# MCU.net
KiCad netlist of a schematic drawn in Altium Designer
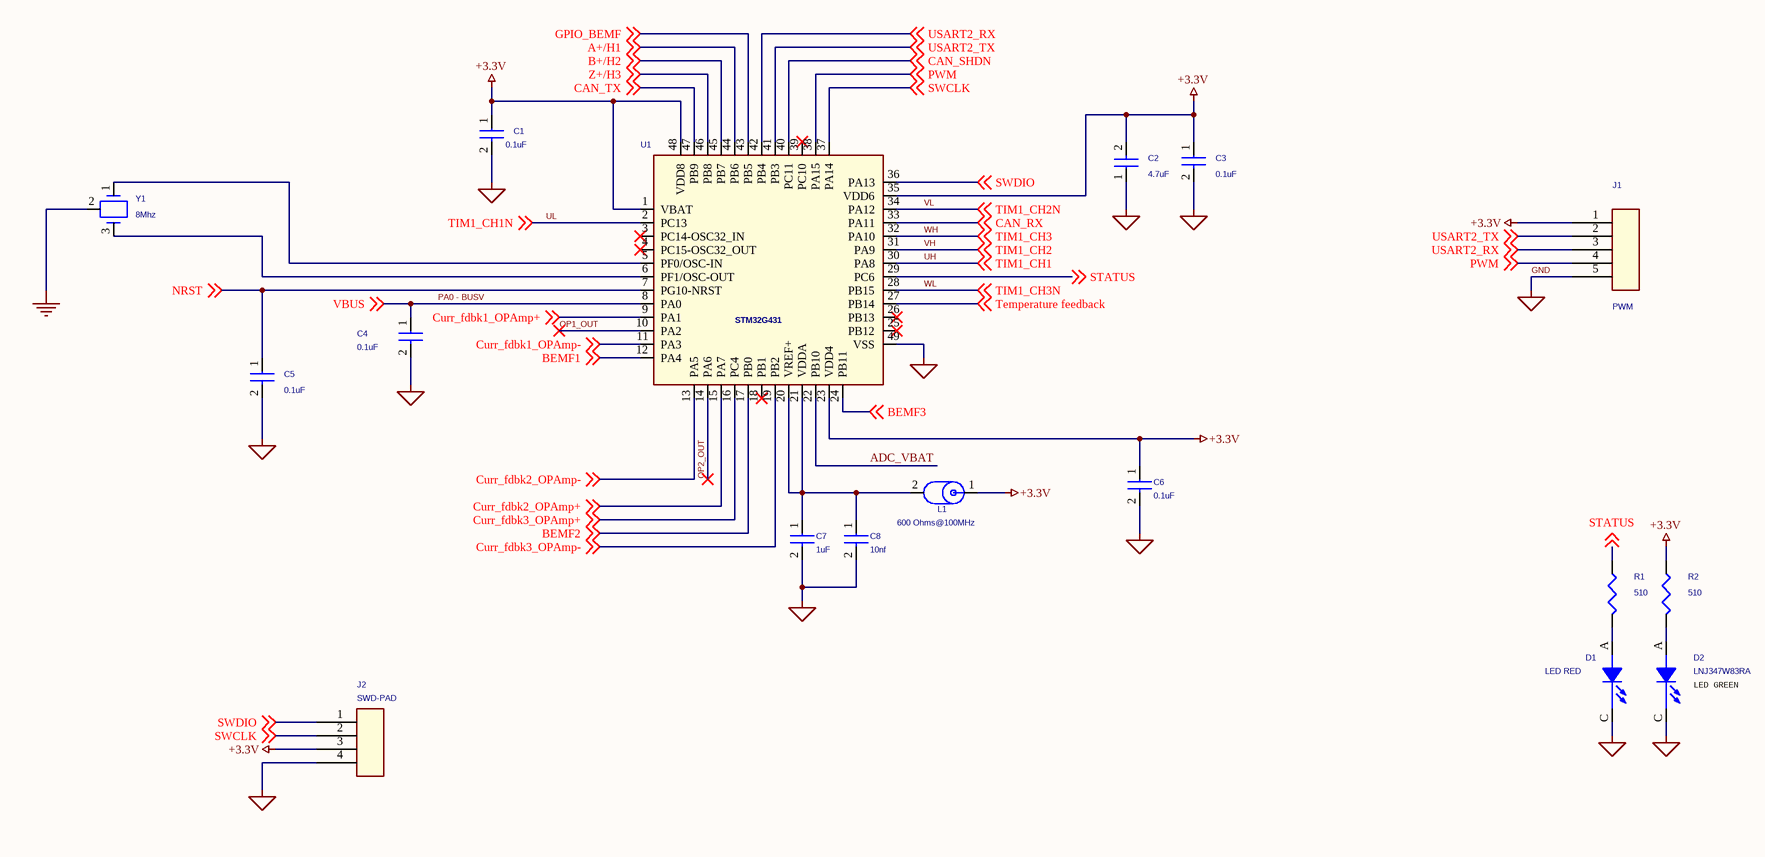
[diagram p0: MCU.SchDoc]

(export (version "E")
  (design (tool "Eeschema 10.0.6"))
  (components
    (comp (ref "C1")
      (value "0.1uF")
      (footprint "C_0402")
      (description "CAP CER 0.1UF 16V X7R 0402")
      (fields (field (name "PART_NUMBER") "CAP-00000053") (field (name "TOLERANCE") "10%"))
      (libsource (lib "*") (part "CAP_Dup1"))
    )
    (comp (ref "C2")
      (value "4.7uF")
      (footprint "C_0603")
      (description "CAP CER 4.7UF 10V X5R 0603")
      (fields (field (name "MANUFACTURER") "Wurth Electronics Inc.") (field (name "TOLERANCE") "20%"))
      (libsource (lib "*") (part "CAP_Dup1"))
    )
    (comp (ref "C3")
      (value "0.1uF")
      (footprint "C_0402")
      (description "CAP CER 0.1UF 16V X7R 0402")
      (fields (field (name "MANUFACTURER") "Wurth Electronics Inc.") (field (name "TOLERANCE") "10%"))
      (libsource (lib "*") (part "CAP_Dup1"))
    )
    (comp (ref "C4")
      (value "0.1uF")
      (footprint "C_0402")
      (description "CAP CER 0.1UF 16V X7R 0402")
      (fields (field (name "MANUFACTURER") "Wurth Electronics Inc.") (field (name "TOLERANCE") "10%"))
      (libsource (lib "*") (part "CAP_Dup1"))
    )
    (comp (ref "C5")
      (value "0.1uF")
      (footprint "C_0402")
      (description "CAP CER 0.1UF 16V X7R 0402")
      (fields (field (name "MANUFACTURER") "Wurth Electronics Inc.") (field (name "TOLERANCE") "10%"))
      (libsource (lib "*") (part "CAP_Dup1"))
    )
    (comp (ref "C6")
      (value "0.1uF")
      (footprint "C_0402")
      (description "CAP CER 0.1UF 16V X7R 0402")
      (fields (field (name "MANUFACTURER") "Wurth Electronics Inc.") (field (name "TOLERANCE") "10%"))
      (libsource (lib "*") (part "CAP_Dup1"))
    )
    (comp (ref "C7")
      (value "1uF")
      (footprint "C_0402")
      (description "CAP CER 1UF 25V X5R 0402")
      (fields (field (name "PART_NUMBER") "CAP-00000006") (field (name "TOLERANCE") "10%"))
      (libsource (lib "*") (part "CAP_Dup1"))
    )
    (comp (ref "C8")
      (value "10nf")
      (footprint "C_0402")
      (description "CAP CER 10000PF 16V X7R 0402")
      (fields (field (name "PART_NUMBER") "TMP-422") (field (name "TOLERANCE") "10%"))
      (libsource (lib "*") (part "CAP_Dup1"))
    )
    (comp (ref "D1")
      (value "LED RED")
      (footprint "D_0402_Led_red")
      (description "DIO, Rectangle with Flat Top, 1.00mm x 0.50mm, VLMS1500-GS08, 20mA, --, --, 0402 (1005 Metric)")
      (fields
        (field (name "PART_NUMBER") "DIO-00000003")
        (field (name "MANUFACTURER") "Vishay Semiconductor Opto Division")
      )
      (libsource (lib "*") (part "LED"))
    )
    (comp (ref "D2")
      (value "LNJ347W83RA")
      (footprint "D_0402_Led_green")
      (description "LED GREEN 0402 SMD")
      (fields
        (field (name "PART_NUMBER") "TMP-187")
        (field (name "MANUFACTURER") "Panasonic Electronic Components")
      )
      (libsource (lib "*") (part "LED"))
    )
    (comp (ref "J1")
      (value "PWM")
      (footprint "SOLDER_PAD_5PIN_SMD")
      (description "SOLDER PADS")
      (libsource (lib "*") (part "CON5"))
    )
    (comp (ref "J2")
      (value "SWD-PAD")
      (footprint "SOLDER_PAD_4PIN_rect_SMD")
      (description "SOLDER PADS")
      (libsource (lib "*") (part "CON4"))
    )
    (comp (ref "L1")
      (value "600 Ohms@100MHz")
      (footprint "L_0402")
      (description "FERRITE BEAD 600 OHM 0402 1LN")
      (fields
        (field (name "MANUFACTURER") "Murata Electronics North America")
        (field (name "PART_NUMBER") "TMP-492")
      )
      (libsource (lib "*") (part "IND_FB"))
    )
    (comp (ref "R1")
      (value "510")
      (footprint "R_0402")
      (description "RES SMD 510 OHM 1% 1/16W 0402")
      (fields (field (name "PART_NUMBER") "TMP-438") (field (name "TOLERANCE") "1%"))
      (libsource (lib "*") (part "RES"))
    )
    (comp (ref "R2")
      (value "510")
      (footprint "R_0402")
      (description "RES SMD 510 OHM 1% 1/16W 0402")
      (fields (field (name "PART_NUMBER") "TMP-438") (field (name "TOLERANCE") "1%"))
      (libsource (lib "*") (part "RES"))
    )
    (comp (ref "U1")
      (value "STM32G431")
      (footprint "qfn49p50_700x700x60l40x25t560n")
      (libsource (lib "*") (part "STM32_LQFP64_6"))
    )
    (comp (ref "Y1")
      (value "8Mhz")
      (footprint "murata_cstce8m00g15c99-r0")
      (description "CER RES 8.0000MHZ 33PF SMD")
      (fields
        (field (name "MANUFACTURER") "Murata Electronics North America")
        (field (name "PART_NUMBER") "TMP-382")
      )
      (libsource (lib "*") (part "resonator"))
    )
  )
  (nets
    (net (code "1") (name "+3.3V") (class "Default")
      (node (ref "C1") (pin "1") (pinfunction "1_1") (pintype "passive"))
      (node (ref "C2") (pin "2") (pinfunction "2_2") (pintype "passive"))
      (node (ref "C3") (pin "1") (pinfunction "1_1") (pintype "passive"))
      (node (ref "C6") (pin "1") (pinfunction "1_1") (pintype "passive"))
      (node (ref "J1") (pin "1") (pinfunction "1_1") (pintype "passive"))
      (node (ref "J2") (pin "3") (pinfunction "3_3") (pintype "passive"))
      (node (ref "L1") (pin "1") (pinfunction "1_1") (pintype "passive"))
      (node (ref "R2") (pin "1") (pinfunction "1_1") (pintype "passive"))
      (node (ref "U1") (pin "1") (pinfunction "VBAT_1") (pintype "passive"))
      (node (ref "U1") (pin "23") (pinfunction "VDD4_23") (pintype "passive"))
      (node (ref "U1") (pin "35") (pinfunction "VDD6_35") (pintype "passive"))
      (node (ref "U1") (pin "48") (pinfunction "VDD8_48") (pintype "passive"))
    )
    (net (code "2") (name "/ADC_VBAT") (class "Default")
      (node (ref "U1") (pin "22") (pinfunction "PB10_22") (pintype "passive"))
    )
    (net (code "3") (name "/OP1_OUT") (class "Default")
      (node (ref "U1") (pin "10") (pinfunction "PA2_10") (pintype "passive+no_connect"))
    )
    (net (code "4") (name "/OP2_OUT") (class "Default")
      (node (ref "U1") (pin "14") (pinfunction "PA6_14") (pintype "passive+no_connect"))
    )
    (net (code "5") (name "A+{slash}H1") (class "Default")
      (node (ref "U1") (pin "44") (pinfunction "PB6_44") (pintype "passive"))
    )
    (net (code "6") (name "B+{slash}H2") (class "Default")
      (node (ref "U1") (pin "45") (pinfunction "PB7_45") (pintype "passive"))
    )
    (net (code "7") (name "BEMF1") (class "Default")
      (node (ref "U1") (pin "12") (pinfunction "PA4_12") (pintype "passive"))
    )
    (net (code "8") (name "BEMF2") (class "Default")
      (node (ref "U1") (pin "17") (pinfunction "PB0_17") (pintype "passive"))
    )
    (net (code "9") (name "BEMF3") (class "Default")
      (node (ref "U1") (pin "24") (pinfunction "PB11_24") (pintype "passive"))
    )
    (net (code "10") (name "CAN_RX") (class "Default")
      (node (ref "U1") (pin "33") (pinfunction "PA11_33") (pintype "passive"))
    )
    (net (code "11") (name "CAN_SHDN") (class "Default")
      (node (ref "U1") (pin "40") (pinfunction "PC11_40") (pintype "passive"))
    )
    (net (code "12") (name "CAN_TX") (class "Default")
      (node (ref "U1") (pin "47") (pinfunction "PB9_47") (pintype "passive"))
    )
    (net (code "13") (name "Curr_fdbk1_OPAmp+") (class "Default")
      (node (ref "U1") (pin "9") (pinfunction "PA1_9") (pintype "passive"))
    )
    (net (code "14") (name "Curr_fdbk1_OPAmp-") (class "Default")
      (node (ref "U1") (pin "11") (pinfunction "PA3_11") (pintype "passive"))
    )
    (net (code "15") (name "Curr_fdbk2_OPAmp+") (class "Default")
      (node (ref "U1") (pin "15") (pinfunction "PA7_15") (pintype "passive"))
    )
    (net (code "16") (name "Curr_fdbk2_OPAmp-") (class "Default")
      (node (ref "U1") (pin "13") (pinfunction "PA5_13") (pintype "passive"))
    )
    (net (code "17") (name "Curr_fdbk3_OPAmp+") (class "Default")
      (node (ref "U1") (pin "16") (pinfunction "PC4_16") (pintype "passive"))
    )
    (net (code "18") (name "Curr_fdbk3_OPAmp-") (class "Default")
      (node (ref "U1") (pin "19") (pinfunction "PB2_19") (pintype "passive"))
    )
    (net (code "19") (name "GND") (class "Default")
      (node (ref "C1") (pin "2") (pinfunction "2_2") (pintype "passive"))
      (node (ref "C2") (pin "1") (pinfunction "1_1") (pintype "passive"))
      (node (ref "C3") (pin "2") (pinfunction "2_2") (pintype "passive"))
      (node (ref "C4") (pin "2") (pinfunction "2_2") (pintype "passive"))
      (node (ref "C5") (pin "2") (pinfunction "2_2") (pintype "passive"))
      (node (ref "C6") (pin "2") (pinfunction "2_2") (pintype "passive"))
      (node (ref "C7") (pin "2") (pinfunction "2_2") (pintype "passive"))
      (node (ref "C8") (pin "2") (pinfunction "2_2") (pintype "passive"))
      (node (ref "D1") (pin "C") (pinfunction "CATHODE_C") (pintype "passive"))
      (node (ref "D2") (pin "C") (pinfunction "CATHODE_C") (pintype "passive"))
      (node (ref "J1") (pin "5") (pinfunction "5_5") (pintype "passive"))
      (node (ref "J2") (pin "4") (pinfunction "4_4") (pintype "passive"))
      (node (ref "U1") (pin "49") (pinfunction "VSS_49") (pintype "passive"))
      (node (ref "Y1") (pin "2") (pinfunction "2_2") (pintype "passive"))
    )
    (net (code "20") (name "GPIO_BEMF") (class "Default")
      (node (ref "U1") (pin "43") (pinfunction "PB5_43") (pintype "passive"))
    )
    (net (code "21") (name "NRST") (class "Default")
      (node (ref "C5") (pin "1") (pinfunction "1_1") (pintype "passive"))
      (node (ref "U1") (pin "7") (pinfunction "PG10-NRST_7") (pintype "passive"))
    )
    (net (code "22") (name "Net-(D1-ANODE)") (class "Default")
      (node (ref "D1") (pin "A") (pinfunction "ANODE_A") (pintype "passive"))
      (node (ref "R1") (pin "2") (pinfunction "2_2") (pintype "passive"))
    )
    (net (code "23") (name "Net-(D2-ANODE)") (class "Default")
      (node (ref "D2") (pin "A") (pinfunction "ANODE_A") (pintype "passive"))
      (node (ref "R2") (pin "2") (pinfunction "2_2") (pintype "passive"))
    )
    (net (code "24") (name "Net-(U1-PF0{slash}OSC-IN)") (class "Default")
      (node (ref "U1") (pin "5") (pinfunction "PF0/OSC-IN_5") (pintype "passive"))
      (node (ref "Y1") (pin "1") (pinfunction "1_1") (pintype "passive"))
    )
    (net (code "25") (name "Net-(U1-PF1{slash}OSC-OUT)") (class "Default")
      (node (ref "U1") (pin "6") (pinfunction "PF1/OSC-OUT_6") (pintype "passive"))
      (node (ref "Y1") (pin "3") (pinfunction "3_3") (pintype "passive"))
    )
    (net (code "26") (name "Net-(U1-VDDA)") (class "Default")
      (node (ref "C7") (pin "1") (pinfunction "1_1") (pintype "passive"))
      (node (ref "C8") (pin "1") (pinfunction "1_1") (pintype "passive"))
      (node (ref "L1") (pin "2") (pinfunction "2_2") (pintype "passive"))
      (node (ref "U1") (pin "20") (pinfunction "VREF+_20") (pintype "passive"))
      (node (ref "U1") (pin "21") (pinfunction "VDDA_21") (pintype "passive"))
    )
    (net (code "27") (name "PWM") (class "Default")
      (node (ref "J1") (pin "4") (pinfunction "4_4") (pintype "passive"))
      (node (ref "U1") (pin "38") (pinfunction "PA15_38") (pintype "passive"))
    )
    (net (code "28") (name "STATUS") (class "Default")
      (node (ref "R1") (pin "1") (pinfunction "1_1") (pintype "passive"))
      (node (ref "U1") (pin "29") (pinfunction "PC6_29") (pintype "passive"))
    )
    (net (code "29") (name "SWCLK") (class "Default")
      (node (ref "J2") (pin "2") (pinfunction "2_2") (pintype "passive"))
      (node (ref "U1") (pin "37") (pinfunction "PA14_37") (pintype "passive"))
    )
    (net (code "30") (name "SWDIO") (class "Default")
      (node (ref "J2") (pin "1") (pinfunction "1_1") (pintype "passive"))
      (node (ref "U1") (pin "36") (pinfunction "PA13_36") (pintype "passive"))
    )
    (net (code "31") (name "TIM1_CH1") (class "Default")
      (node (ref "U1") (pin "30") (pinfunction "PA8_30") (pintype "passive"))
    )
    (net (code "32") (name "TIM1_CH1N") (class "Default")
      (node (ref "U1") (pin "2") (pinfunction "PC13_2") (pintype "passive"))
    )
    (net (code "33") (name "TIM1_CH2") (class "Default")
      (node (ref "U1") (pin "31") (pinfunction "PA9_31") (pintype "passive"))
    )
    (net (code "34") (name "TIM1_CH2N") (class "Default")
      (node (ref "U1") (pin "34") (pinfunction "PA12_34") (pintype "passive"))
    )
    (net (code "35") (name "TIM1_CH3") (class "Default")
      (node (ref "U1") (pin "32") (pinfunction "PA10_32") (pintype "passive"))
    )
    (net (code "36") (name "TIM1_CH3N") (class "Default")
      (node (ref "U1") (pin "28") (pinfunction "PB15_28") (pintype "passive"))
    )
    (net (code "37") (name "Temperature feedback") (class "Default")
      (node (ref "U1") (pin "27") (pinfunction "PB14_27") (pintype "passive"))
    )
    (net (code "38") (name "USART2_RX") (class "Default")
      (node (ref "J1") (pin "3") (pinfunction "3_3") (pintype "passive"))
      (node (ref "U1") (pin "42") (pinfunction "PB4_42") (pintype "passive"))
    )
    (net (code "39") (name "USART2_TX") (class "Default")
      (node (ref "J1") (pin "2") (pinfunction "2_2") (pintype "passive"))
      (node (ref "U1") (pin "41") (pinfunction "PB3_41") (pintype "passive"))
    )
    (net (code "40") (name "VBUS") (class "Default")
      (node (ref "C4") (pin "1") (pinfunction "1_1") (pintype "passive"))
      (node (ref "U1") (pin "8") (pinfunction "PA0_8") (pintype "passive"))
    )
    (net (code "41") (name "Z+{slash}H3") (class "Default")
      (node (ref "U1") (pin "46") (pinfunction "PB8_46") (pintype "passive"))
    )
    (net (code "42") (name "unconnected-(U1-PB1-Pad18)") (class "Default")
      (node (ref "U1") (pin "18") (pinfunction "PB1_18") (pintype "passive+no_connect"))
    )
    (net (code "43") (name "unconnected-(U1-PB12-Pad25)") (class "Default")
      (node (ref "U1") (pin "25") (pinfunction "PB12_25") (pintype "passive+no_connect"))
    )
    (net (code "44") (name "unconnected-(U1-PB13-Pad26)") (class "Default")
      (node (ref "U1") (pin "26") (pinfunction "PB13_26") (pintype "passive+no_connect"))
    )
    (net (code "45") (name "unconnected-(U1-PC10-Pad39)") (class "Default")
      (node (ref "U1") (pin "39") (pinfunction "PC10_39") (pintype "passive+no_connect"))
    )
    (net (code "46") (name "unconnected-(U1-PC14-OSC32_IN-Pad3)") (class "Default")
      (node (ref "U1") (pin "3") (pinfunction "PC14-OSC32_IN_3") (pintype "passive+no_connect"))
    )
    (net (code "47") (name "unconnected-(U1-PC15-OSC32_OUT-Pad4)") (class "Default")
      (node (ref "U1") (pin "4") (pinfunction "PC15-OSC32_OUT_4") (pintype "passive+no_connect"))
    )
  )
)
